# PSRAM.net
KiCad netlist of a schematic drawn in Altium Designer
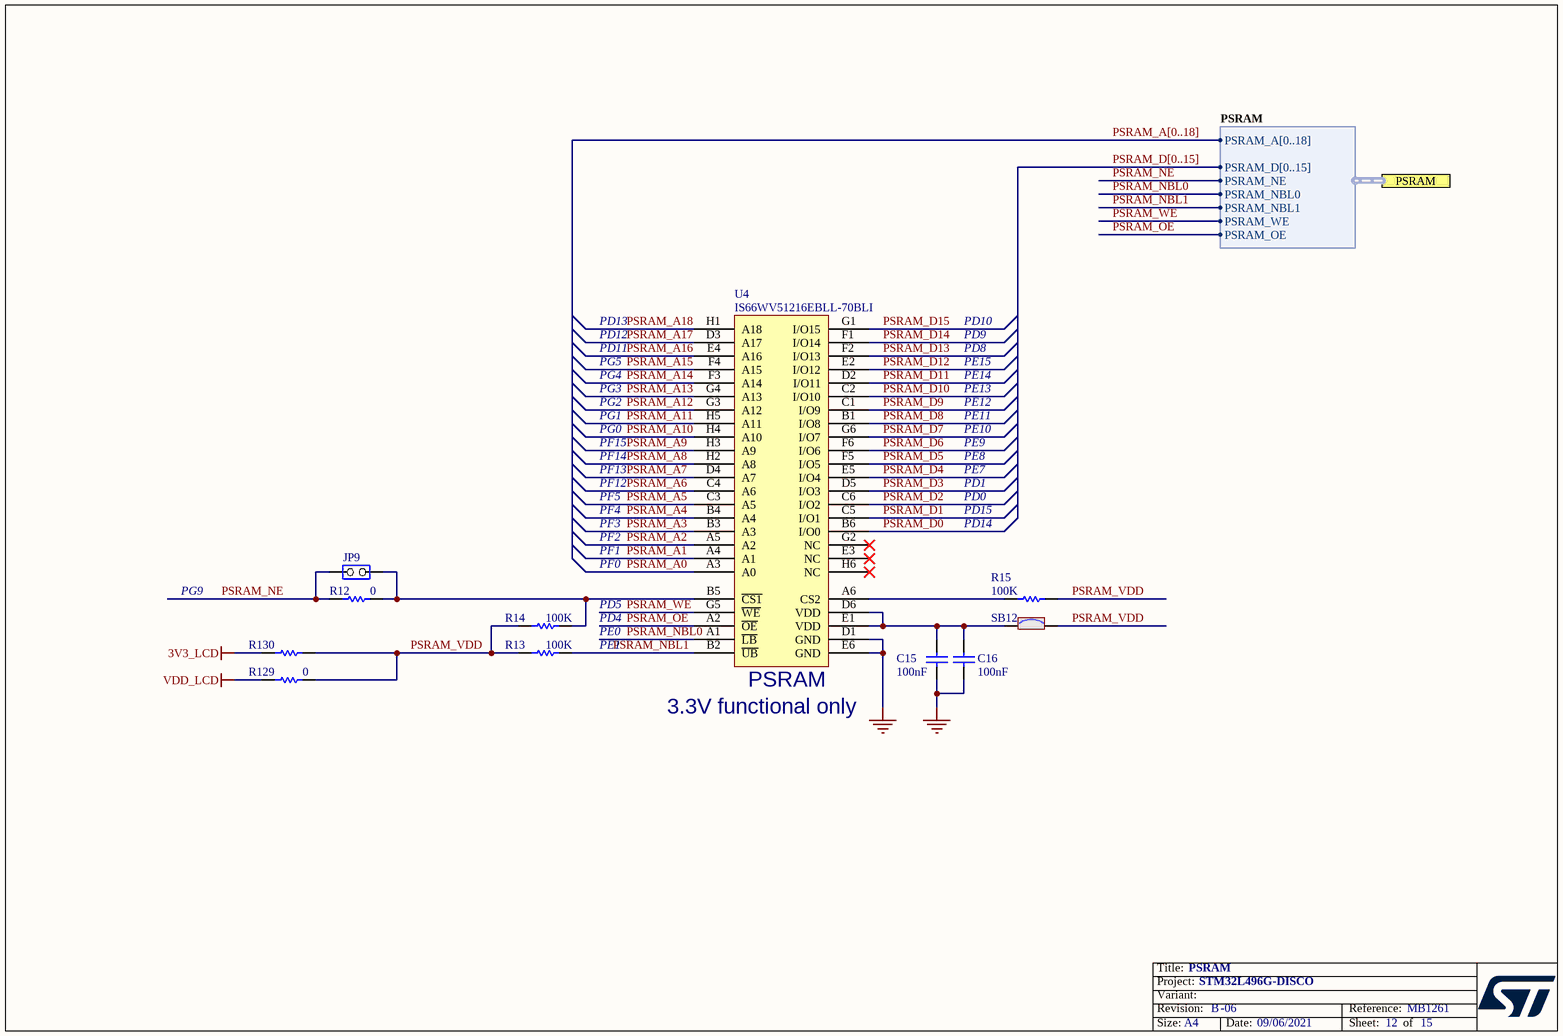
[diagram p0: PSRAM.SchDoc]

(export (version "E")
  (design (tool "Eeschema 10.0.6"))
  (components
    (comp (ref "C15")
      (value "100nF")
      (footprint "0603C")
      (description "Capacitor,100nF,10%,16V,X7R,0603,YAGEO")
      (fields (field (name "Comment") "CC0603KRX7R7BB104") (field (name "PUBLISHER") "Altium Limited"))
      (libsource (lib "Miscellaneous Devices") (part "Cap"))
    )
    (comp (ref "C16")
      (value "100nF")
      (footprint "0603C")
      (description "Capacitor,100nF,10%,16V,X7R,0603,YAGEO")
      (fields (field (name "Comment") "CC0603KRX7R7BB104") (field (name "PUBLISHER") "Altium Limited"))
      (libsource (lib "Miscellaneous Devices") (part "Cap"))
    )
    (comp (ref "JP9") (value "2 PIN Jumper") (footprint "SIP2") (libsource (lib "*") (part "JP2")))
    (comp (ref "R12")
      (value "0")
      (footprint "0603R")
      (description "Resistor, 0 ,0603,1%,YAGEO")
      (fields (field (name "PUBLISHER") "Altium Limited"))
      (libsource (lib "Miscellaneous Devices") (part "res1"))
    )
    (comp (ref "R13")
      (value "100K")
      (footprint "0603R")
      (description "Resistor,100K,0603,1%,YAGEO")
      (fields (field (name "Comment") "RC0603FR-07100KL") (field (name "PUBLISHER") "Altium Limited"))
      (libsource (lib "Miscellaneous Devices") (part "res1"))
    )
    (comp (ref "R14")
      (value "100K")
      (footprint "0603R")
      (description "Resistor,100K,0603,1%,YAGEO")
      (fields (field (name "Comment") "RC0603FR-07100KL") (field (name "PUBLISHER") "Altium Limited"))
      (libsource (lib "Miscellaneous Devices") (part "res1"))
    )
    (comp (ref "R15")
      (value "100K")
      (footprint "0603R")
      (description "Resistor,100K,0603,1%,YAGEO")
      (fields (field (name "Comment") "RC0603FR-07100KL") (field (name "PUBLISHER") "Altium Limited"))
      (libsource (lib "Miscellaneous Devices") (part "res1"))
    )
    (comp (ref "R129")
      (value "0")
      (footprint "0603R")
      (description "Resistor, 0 ,0603,1%,YAGEO")
      (fields (field (name "Comment") "RC0603JR-070RL") (field (name "PUBLISHER") "Altium Limited"))
      (libsource (lib "Miscellaneous Devices") (part "res1"))
    )
    (comp (ref "R130")
      (value "~")
      (footprint "0603R")
      (description "Resistor, 0 ,0603,1%,YAGEO")
      (fields (field (name "PUBLISHER") "Altium Limited"))
      (libsource (lib "Miscellaneous Devices") (part "res1"))
    )
    (comp (ref "SB12")
      (value "Solder Bridge ON")
      (footprint "SB_0603")
      (libsource (lib "MCD_TOOLS") (part "SB_ON"))
    )
    (comp (ref "U4")
      (value "IS66WV51216EBLL-70BLI")
      (footprint "FBGA48_0R75_6X8")
      (description "8M Bit static RAMs organized as 512K words by  16 bits.")
      (libsource (lib "Big Orga") (part "IS66WV51216EBLL-70BLI"))
    )
  )
  (nets
    (net (code "2") (name "/PSRAM_A0") (class "Default")
      (node (ref "U4") (pin "A3") (pinfunction "A0_A3") (pintype "passive"))
    )
    (net (code "3") (name "/PSRAM_A1") (class "Default")
      (node (ref "U4") (pin "A4") (pinfunction "A1_A4") (pintype "passive"))
    )
    (net (code "4") (name "/PSRAM_A2") (class "Default")
      (node (ref "U4") (pin "A5") (pinfunction "A2_A5") (pintype "passive"))
    )
    (net (code "5") (name "/PSRAM_A3") (class "Default")
      (node (ref "U4") (pin "B3") (pinfunction "A3_B3") (pintype "passive"))
    )
    (net (code "6") (name "/PSRAM_A4") (class "Default")
      (node (ref "U4") (pin "B4") (pinfunction "A4_B4") (pintype "passive"))
    )
    (net (code "7") (name "/PSRAM_A5") (class "Default")
      (node (ref "U4") (pin "C3") (pinfunction "A5_C3") (pintype "passive"))
    )
    (net (code "8") (name "/PSRAM_A6") (class "Default")
      (node (ref "U4") (pin "C4") (pinfunction "A6_C4") (pintype "passive"))
    )
    (net (code "9") (name "/PSRAM_A7") (class "Default")
      (node (ref "U4") (pin "D4") (pinfunction "A7_D4") (pintype "passive"))
    )
    (net (code "10") (name "/PSRAM_A8") (class "Default")
      (node (ref "U4") (pin "H2") (pinfunction "A8_H2") (pintype "passive"))
    )
    (net (code "11") (name "/PSRAM_A9") (class "Default")
      (node (ref "U4") (pin "H3") (pinfunction "A9_H3") (pintype "passive"))
    )
    (net (code "12") (name "/PSRAM_A10") (class "Default")
      (node (ref "U4") (pin "H4") (pinfunction "A10_H4") (pintype "passive"))
    )
    (net (code "13") (name "/PSRAM_A11") (class "Default")
      (node (ref "U4") (pin "H5") (pinfunction "A11_H5") (pintype "passive"))
    )
    (net (code "14") (name "/PSRAM_A12") (class "Default")
      (node (ref "U4") (pin "G3") (pinfunction "A12_G3") (pintype "passive"))
    )
    (net (code "15") (name "/PSRAM_A13") (class "Default")
      (node (ref "U4") (pin "G4") (pinfunction "A13_G4") (pintype "passive"))
    )
    (net (code "16") (name "/PSRAM_A14") (class "Default")
      (node (ref "U4") (pin "F3") (pinfunction "A14_F3") (pintype "passive"))
    )
    (net (code "17") (name "/PSRAM_A15") (class "Default")
      (node (ref "U4") (pin "F4") (pinfunction "A15_F4") (pintype "passive"))
    )
    (net (code "18") (name "/PSRAM_A16") (class "Default")
      (node (ref "U4") (pin "E4") (pinfunction "A16_E4") (pintype "passive"))
    )
    (net (code "19") (name "/PSRAM_A17") (class "Default")
      (node (ref "U4") (pin "D3") (pinfunction "A17_D3") (pintype "passive"))
    )
    (net (code "20") (name "/PSRAM_A18") (class "Default")
      (node (ref "U4") (pin "H1") (pinfunction "A18_H1") (pintype "passive"))
    )
    (net (code "22") (name "/PSRAM_D0") (class "Default")
      (node (ref "U4") (pin "B6") (pinfunction "I/O0_B6") (pintype "passive"))
    )
    (net (code "23") (name "/PSRAM_D1") (class "Default")
      (node (ref "U4") (pin "C5") (pinfunction "I/O1_C5") (pintype "passive"))
    )
    (net (code "24") (name "/PSRAM_D2") (class "Default")
      (node (ref "U4") (pin "C6") (pinfunction "I/O2_C6") (pintype "passive"))
    )
    (net (code "25") (name "/PSRAM_D3") (class "Default")
      (node (ref "U4") (pin "D5") (pinfunction "I/O3_D5") (pintype "passive"))
    )
    (net (code "26") (name "/PSRAM_D4") (class "Default")
      (node (ref "U4") (pin "E5") (pinfunction "I/O4_E5") (pintype "passive"))
    )
    (net (code "27") (name "/PSRAM_D5") (class "Default")
      (node (ref "U4") (pin "F5") (pinfunction "I/O5_F5") (pintype "passive"))
    )
    (net (code "28") (name "/PSRAM_D6") (class "Default")
      (node (ref "U4") (pin "F6") (pinfunction "I/O6_F6") (pintype "passive"))
    )
    (net (code "29") (name "/PSRAM_D7") (class "Default")
      (node (ref "U4") (pin "G6") (pinfunction "I/O7_G6") (pintype "passive"))
    )
    (net (code "30") (name "/PSRAM_D8") (class "Default")
      (node (ref "U4") (pin "B1") (pinfunction "I/O8_B1") (pintype "passive"))
    )
    (net (code "31") (name "/PSRAM_D9") (class "Default")
      (node (ref "U4") (pin "C1") (pinfunction "I/O9_C1") (pintype "passive"))
    )
    (net (code "32") (name "/PSRAM_D10") (class "Default")
      (node (ref "U4") (pin "C2") (pinfunction "I/O10_C2") (pintype "passive"))
    )
    (net (code "33") (name "/PSRAM_D11") (class "Default")
      (node (ref "U4") (pin "D2") (pinfunction "I/O11_D2") (pintype "passive"))
    )
    (net (code "34") (name "/PSRAM_D12") (class "Default")
      (node (ref "U4") (pin "E2") (pinfunction "I/O12_E2") (pintype "passive"))
    )
    (net (code "35") (name "/PSRAM_D13") (class "Default")
      (node (ref "U4") (pin "F2") (pinfunction "I/O13_F2") (pintype "passive"))
    )
    (net (code "36") (name "/PSRAM_D14") (class "Default")
      (node (ref "U4") (pin "F1") (pinfunction "I/O14_F1") (pintype "passive"))
    )
    (net (code "37") (name "/PSRAM_D15") (class "Default")
      (node (ref "U4") (pin "G1") (pinfunction "I/O15_G1") (pintype "passive"))
    )
    (net (code "39") (name "/PSRAM_NBL0") (class "Default")
      (node (ref "U4") (pin "A1") (pinfunction "~{LB}_A1") (pintype "passive"))
    )
    (net (code "40") (name "/PSRAM_NBL1") (class "Default")
      (node (ref "R13") (pin "1") (pinfunction "1_1") (pintype "passive"))
      (node (ref "U4") (pin "B2") (pinfunction "~{UB}_B2") (pintype "passive"))
    )
    (net (code "41") (name "/PSRAM_NE") (class "Default")
      (node (ref "JP9") (pin "1") (pinfunction "COMMON_1") (pintype "passive"))
      (node (ref "R12") (pin "2") (pinfunction "2_2") (pintype "passive"))
    )
    (net (code "42") (name "/PSRAM_OE") (class "Default")
      (node (ref "U4") (pin "A2") (pinfunction "~{OE}_A2") (pintype "passive"))
    )
    (net (code "43") (name "/PSRAM_VDD") (class "Default")
      (node (ref "R129") (pin "1") (pinfunction "1_1") (pintype "passive"))
      (node (ref "R13") (pin "2") (pinfunction "2_2") (pintype "passive"))
      (node (ref "R130") (pin "1") (pinfunction "1_1") (pintype "passive"))
      (node (ref "R14") (pin "2") (pinfunction "2_2") (pintype "passive"))
      (node (ref "R15") (pin "1") (pinfunction "1_1") (pintype "passive"))
      (node (ref "SB12") (pin "2") (pinfunction "2_2") (pintype "passive"))
    )
    (net (code "44") (name "/PSRAM_WE") (class "Default")
      (node (ref "U4") (pin "G5") (pinfunction "~{WE}_G5") (pintype "passive"))
    )
    (net (code "46") (name "3V3_LCD") (class "Default")
      (node (ref "R130") (pin "2") (pinfunction "2_2") (pintype "passive"))
    )
    (net (code "47") (name "GND") (class "Default")
      (node (ref "C15") (pin "2") (pinfunction "2_2") (pintype "passive"))
      (node (ref "C16") (pin "2") (pinfunction "2_2") (pintype "passive"))
      (node (ref "U4") (pin "D1") (pinfunction "GND_D1") (pintype "passive"))
      (node (ref "U4") (pin "E6") (pinfunction "GND_E6") (pintype "passive"))
    )
    (net (code "48") (name "Net-(C15-Pad1)") (class "Default")
      (node (ref "C15") (pin "1") (pinfunction "1_1") (pintype "passive"))
      (node (ref "C16") (pin "1") (pinfunction "1_1") (pintype "passive"))
      (node (ref "SB12") (pin "1") (pinfunction "1_1") (pintype "passive"))
      (node (ref "U4") (pin "D6") (pinfunction "VDD_D6") (pintype "passive"))
      (node (ref "U4") (pin "E1") (pinfunction "VDD_E1") (pintype "passive"))
    )
    (net (code "49") (name "Net-(JP9-NO)") (class "Default")
      (node (ref "JP9") (pin "2") (pinfunction "NO_2") (pintype "passive"))
      (node (ref "R12") (pin "1") (pinfunction "1_1") (pintype "passive"))
      (node (ref "R14") (pin "1") (pinfunction "1_1") (pintype "passive"))
      (node (ref "U4") (pin "B5") (pinfunction "~{CS1}_B5") (pintype "passive"))
    )
    (net (code "50") (name "Net-(U4-CS2)") (class "Default")
      (node (ref "R15") (pin "2") (pinfunction "2_2") (pintype "passive"))
      (node (ref "U4") (pin "A6") (pinfunction "CS2_A6") (pintype "passive"))
    )
    (net (code "51") (name "VDD_LCD") (class "Default")
      (node (ref "R129") (pin "2") (pinfunction "2_2") (pintype "passive"))
    )
    (net (code "52") (name "unconnected-(U4-NC-PadE3)") (class "Default")
      (node (ref "U4") (pin "E3") (pinfunction "NC_E3") (pintype "passive+no_connect"))
    )
    (net (code "53") (name "unconnected-(U4-NC-PadG2)") (class "Default")
      (node (ref "U4") (pin "G2") (pinfunction "NC_G2") (pintype "passive+no_connect"))
    )
    (net (code "54") (name "unconnected-(U4-NC-PadH6)") (class "Default")
      (node (ref "U4") (pin "H6") (pinfunction "NC_H6") (pintype "passive+no_connect"))
    )
  )
)
